# Sheet1.net
KiCad netlist of a schematic drawn in Altium Designer
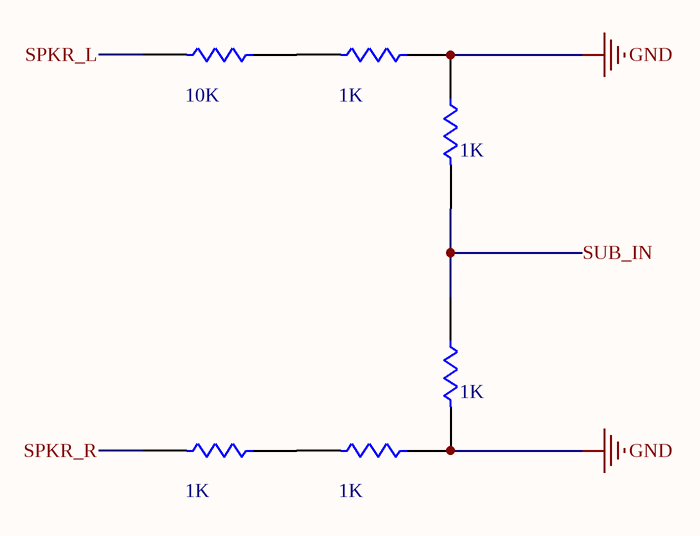
[diagram p0: Sheet1.SchDoc]

(export (version "E")
  (design (tool "Eeschema 10.0.6"))
  (components
    (comp (ref "R1")
      (value "1K")
      (footprint "SOIC16_N")
      (description "Isolated Resistor Network - Parts")
      (fields (field (name "Comment") "Res Pack1") (field (name "PUBLISHER") "Altium Limited"))
      (libsource (lib "") (part "Res Pack1_3"))
    )
    (comp (ref "R2")
      (value "1K")
      (footprint "SOIC16_N")
      (description "Isolated Resistor Network - Parts")
      (fields (field (name "Comment") "Res Pack1") (field (name "PUBLISHER") "Altium Limited"))
      (libsource (lib "") (part "Res Pack1_1"))
    )
    (comp (ref "R3")
      (value "1K")
      (footprint "SOIC16_N")
      (description "Isolated Resistor Network - Parts")
      (fields (field (name "Comment") "Res Pack1") (field (name "PUBLISHER") "Altium Limited"))
      (libsource (lib "") (part "Res Pack1_5"))
    )
    (comp (ref "R5")
      (value "1K")
      (footprint "SOIC16_N")
      (description "Isolated Resistor Network - Parts")
      (fields (field (name "Comment") "Res Pack1") (field (name "PUBLISHER") "Altium Limited"))
      (libsource (lib "") (part "Res Pack1_2"))
    )
    (comp (ref "R6")
      (value "1K")
      (footprint "SOIC16_N")
      (description "Isolated Resistor Network - Parts")
      (fields (field (name "Comment") "Res Pack1") (field (name "PUBLISHER") "Altium Limited"))
      (libsource (lib "Miscellaneous Devices") (part "Res Pack1"))
    )
  )
  (nets
    (net (code "1") (name "/SPKR_L") (class "Default")
      (node (ref "R1") (pin "1") (pinfunction "1_1") (pintype "passive"))
    )
    (net (code "2") (name "/SPKR_R") (class "Default")
      (node (ref "R1") (pin "2") (pinfunction "2_2") (pintype "passive"))
    )
    (net (code "3") (name "/SUB_IN") (class "Default")
      (node (ref "R5") (pin "5") (pinfunction "5_5") (pintype "passive"))
      (node (ref "R6") (pin "11") (pinfunction "11_11") (pintype "passive"))
    )
    (net (code "4") (name "GND") (class "Default")
      (node (ref "R2") (pin "15") (pinfunction "15_15") (pintype "passive"))
      (node (ref "R3") (pin "13") (pinfunction "13_13") (pintype "passive"))
      (node (ref "R5") (pin "12") (pinfunction "12_12") (pintype "passive"))
      (node (ref "R6") (pin "6") (pinfunction "6_6") (pintype "passive"))
    )
    (net (code "5") (name "Net-(R1-Pad15)") (class "Default")
      (node (ref "R1") (pin "15") (pinfunction "15_15") (pintype "passive"))
      (node (ref "R3") (pin "4") (pinfunction "4_4") (pintype "passive"))
    )
    (net (code "6") (name "Net-(R1-Pad16)") (class "Default")
      (node (ref "R1") (pin "16") (pinfunction "16_16") (pintype "passive"))
      (node (ref "R2") (pin "2") (pinfunction "2_2") (pintype "passive"))
    )
  )
)
